# Aux_Power_Board_V1_1.net
KiCad netlist of a schematic drawn in EAGLE
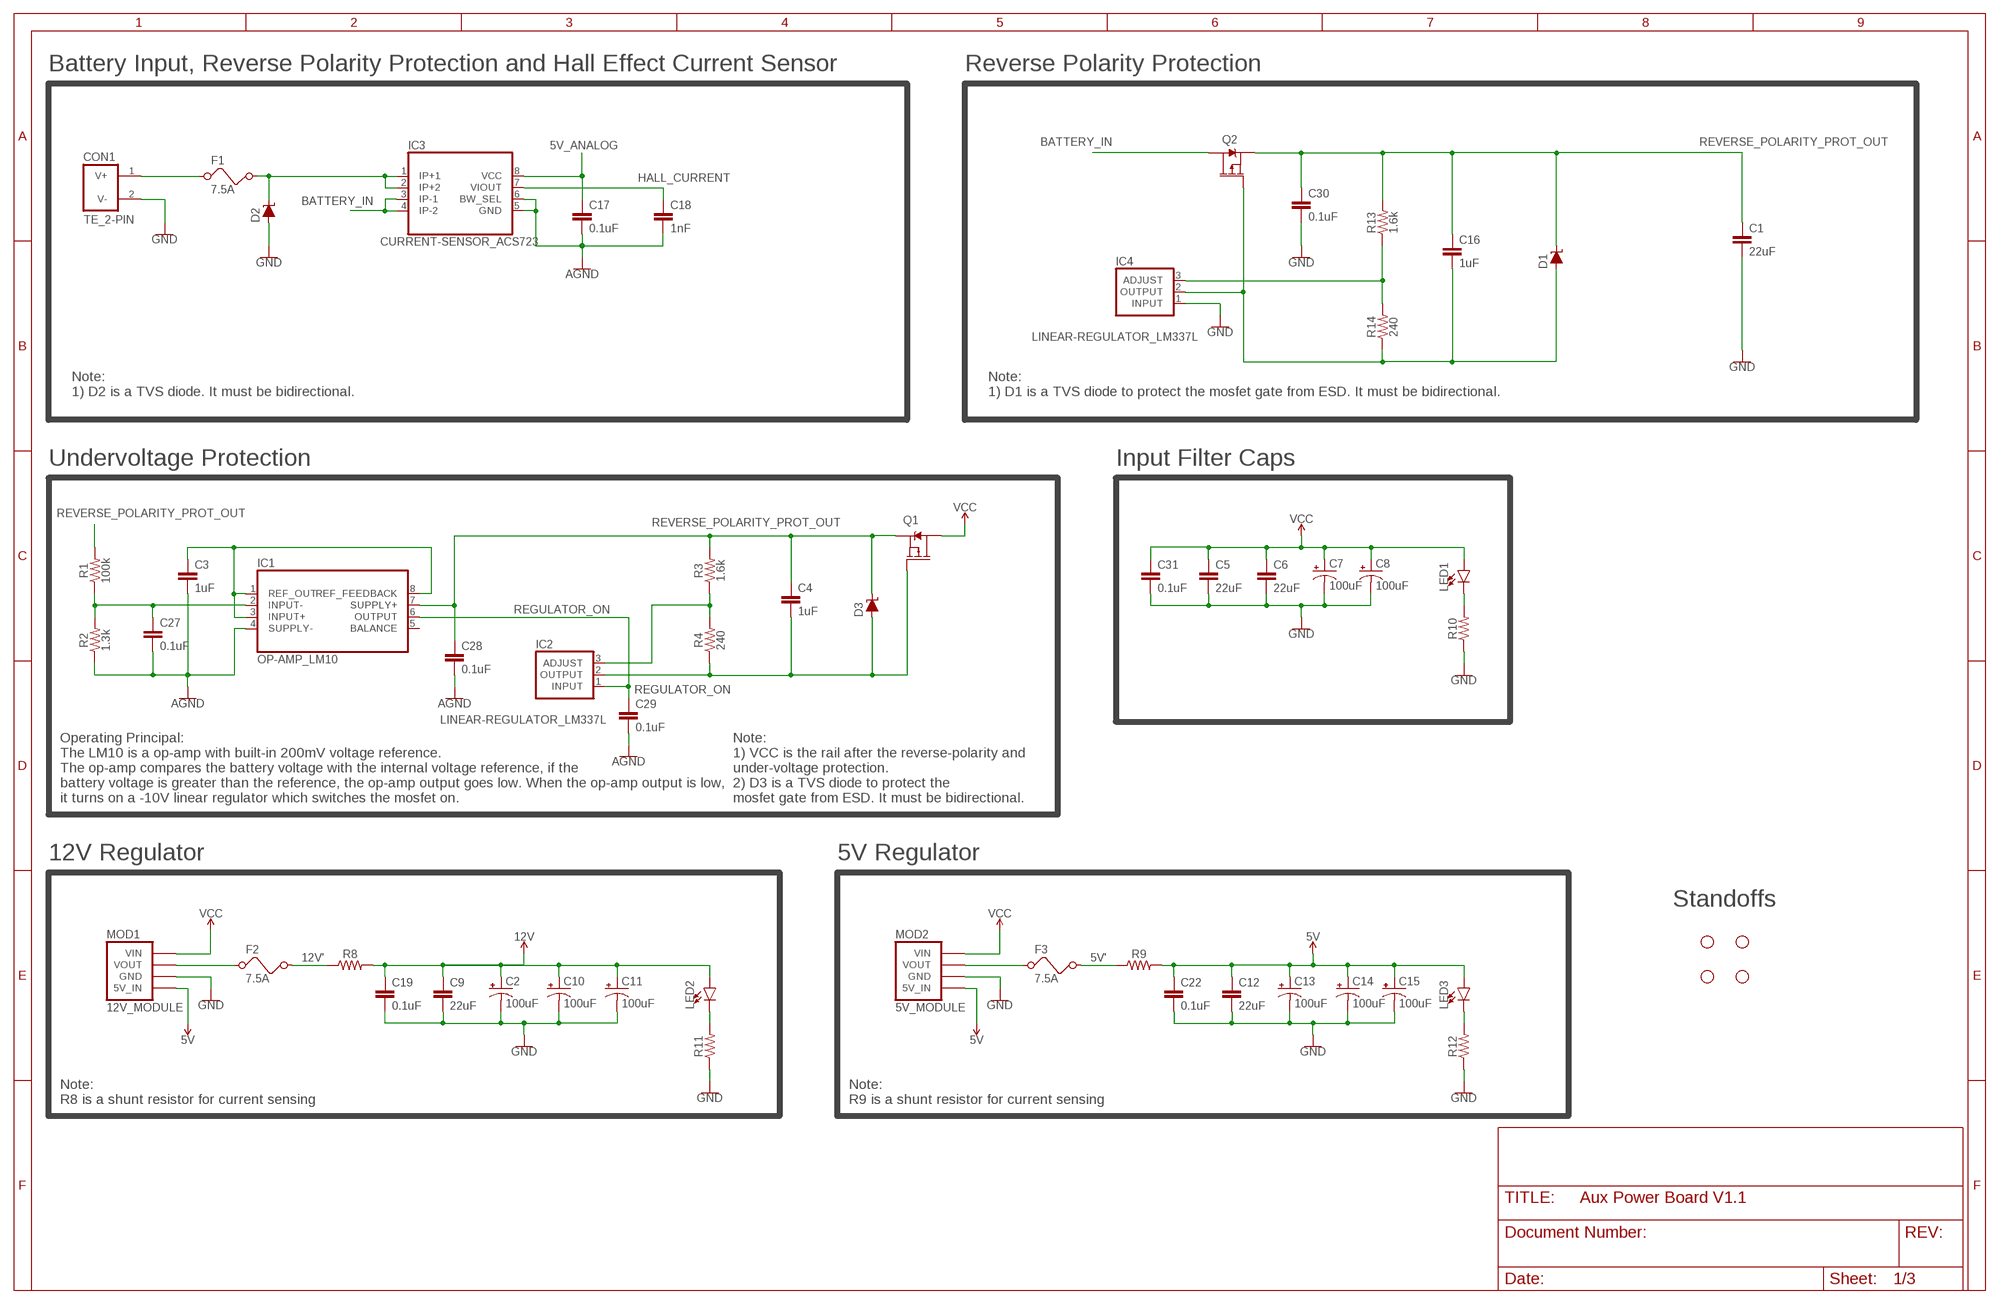
[diagram p0: schematic, sheet 1]
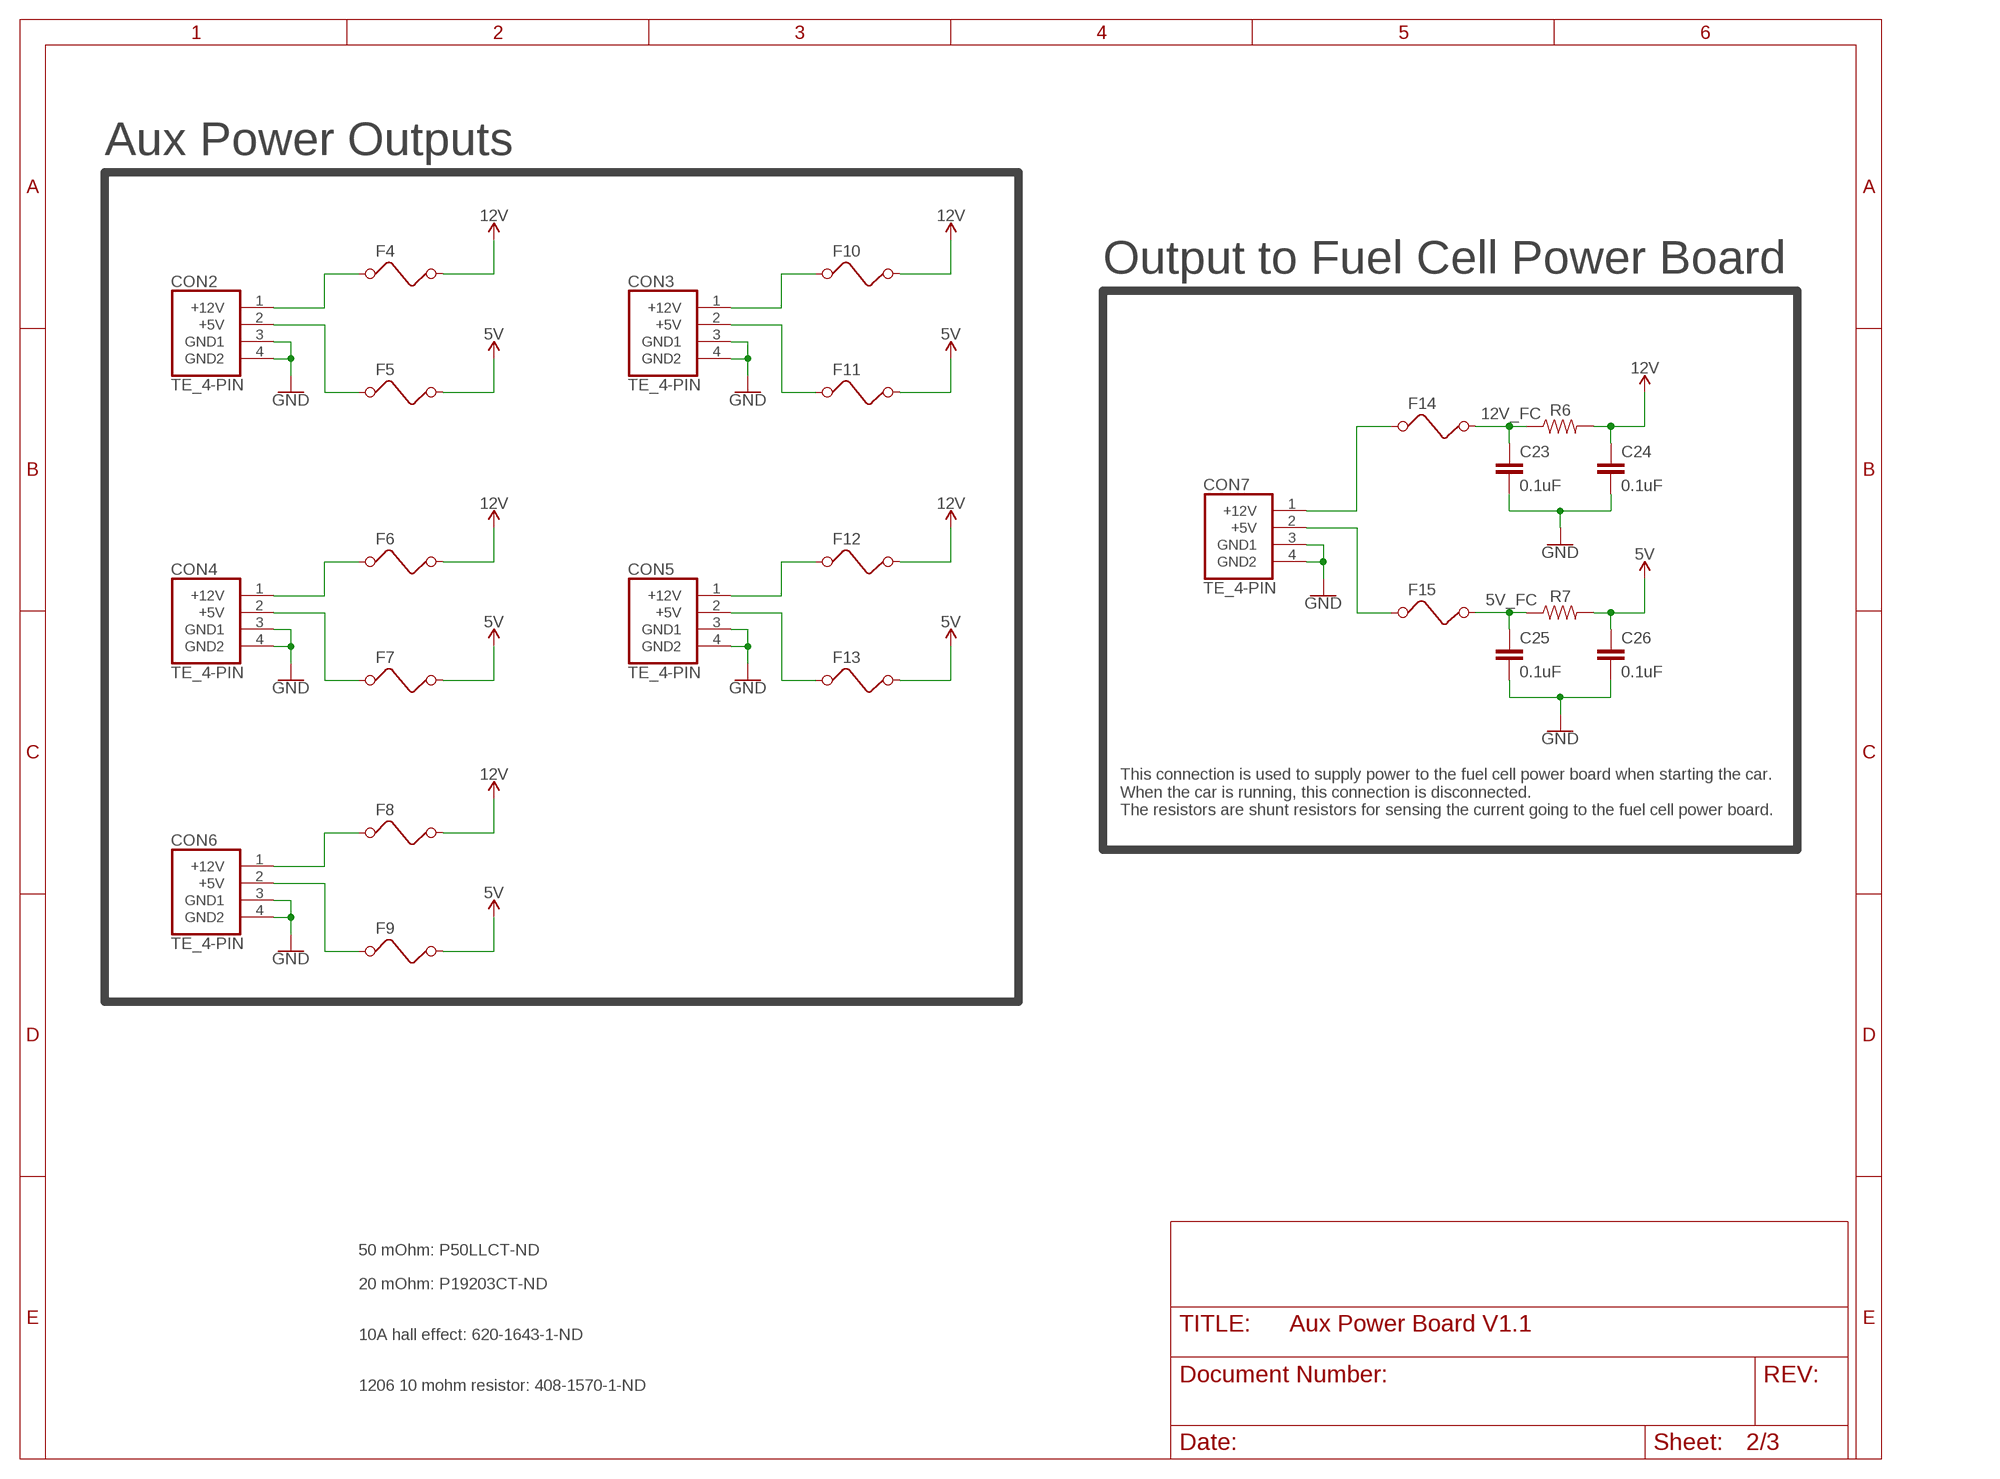
[diagram p1: schematic, sheet 2]
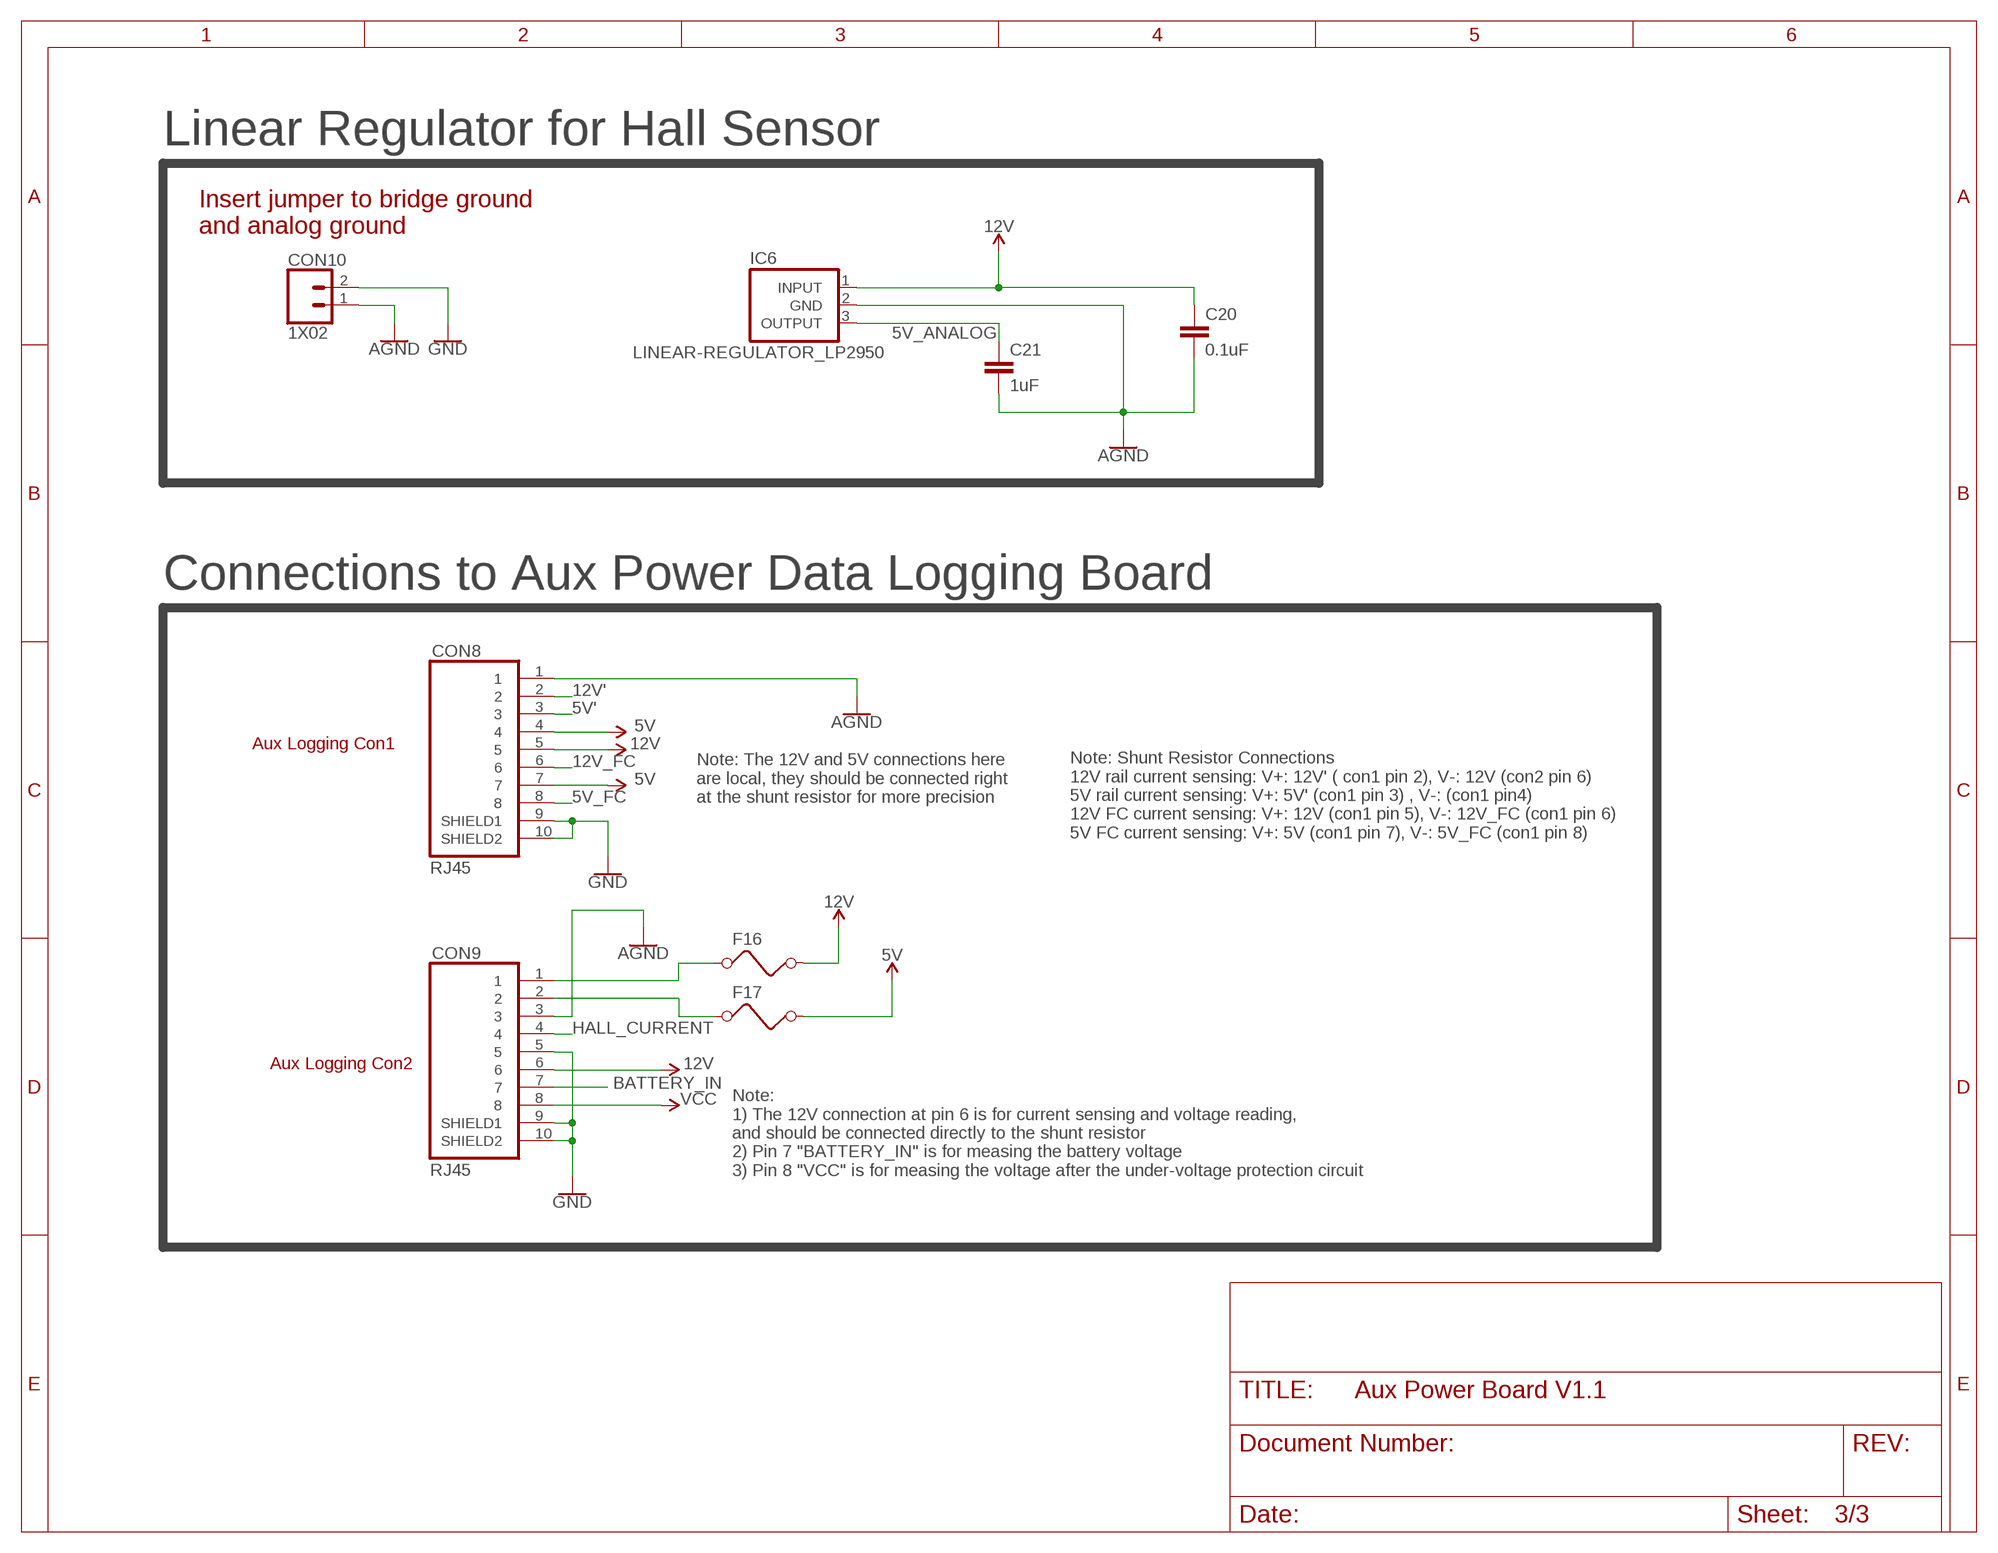
[diagram p2: schematic, sheet 3]

(export (version "E")
  (design (tool "Eeschema 10.0.6"))
  (components
    (comp (ref "C20")
      (value "0.1uF")
      (footprint "eagle-import:0805")
      (libsource (lib "eagle-import") (part "CAPACITOR_0805"))
    )
    (comp (ref "C21")
      (value "1uF")
      (footprint "eagle-import:0805")
      (libsource (lib "eagle-import") (part "CAPACITOR_0805"))
    )
    (comp (ref "CON8")
      (value "RJ45")
      (footprint "eagle-import:RJ45")
      (libsource (lib "eagle-import") (part "RJ45"))
    )
    (comp (ref "CON9")
      (value "RJ45")
      (footprint "eagle-import:RJ45")
      (libsource (lib "eagle-import") (part "RJ45"))
    )
    (comp (ref "CON10")
      (value "1X02")
      (footprint "eagle-import:1X02")
      (libsource (lib "eagle-import") (part "1X02"))
    )
    (comp (ref "F16")
      (value "FUSE_1210")
      (footprint "eagle-import:1210")
      (libsource (lib "eagle-import") (part "FUSE_1210"))
    )
    (comp (ref "F17")
      (value "FUSE_1210")
      (footprint "eagle-import:1210")
      (libsource (lib "eagle-import") (part "FUSE_1210"))
    )
    (comp (ref "IC6")
      (value "LINEAR-REGULATOR_LP2950")
      (footprint "eagle-import:TO92")
      (libsource (lib "eagle-import") (part "LINEAR-REGULATOR_LP2950"))
    )
    (comp (ref "C1")
      (value "22uF")
      (footprint "eagle-import:1210")
      (libsource (lib "eagle-import") (part "CAPACITOR_1210"))
    )
    (comp (ref "C2")
      (value "100uF")
      (footprint "eagle-import:CAPACITOR_100UF_50V")
      (libsource (lib "eagle-import") (part "CAPACITOR_ELECTROLYTIC_100UF"))
    )
    (comp (ref "C3")
      (value "1uF")
      (footprint "eagle-import:0805")
      (libsource (lib "eagle-import") (part "CAPACITOR_0805"))
    )
    (comp (ref "C4")
      (value "1uF")
      (footprint "eagle-import:0805")
      (libsource (lib "eagle-import") (part "CAPACITOR_0805"))
    )
    (comp (ref "C5")
      (value "22uF")
      (footprint "eagle-import:1210")
      (libsource (lib "eagle-import") (part "CAPACITOR_1210"))
    )
    (comp (ref "C6")
      (value "22uF")
      (footprint "eagle-import:1210")
      (libsource (lib "eagle-import") (part "CAPACITOR_1210"))
    )
    (comp (ref "C7")
      (value "100uF")
      (footprint "eagle-import:CAPACITOR_100UF_50V")
      (libsource (lib "eagle-import") (part "CAPACITOR_ELECTROLYTIC_100UF"))
    )
    (comp (ref "C8")
      (value "100uF")
      (footprint "eagle-import:CAPACITOR_100UF_50V")
      (libsource (lib "eagle-import") (part "CAPACITOR_ELECTROLYTIC_100UF"))
    )
    (comp (ref "C9")
      (value "22uF")
      (footprint "eagle-import:0805")
      (libsource (lib "eagle-import") (part "CAPACITOR_0805"))
    )
    (comp (ref "C10")
      (value "100uF")
      (footprint "eagle-import:CAPACITOR_100UF_50V")
      (libsource (lib "eagle-import") (part "CAPACITOR_ELECTROLYTIC_100UF"))
    )
    (comp (ref "C11")
      (value "100uF")
      (footprint "eagle-import:CAPACITOR_100UF_50V")
      (libsource (lib "eagle-import") (part "CAPACITOR_ELECTROLYTIC_100UF"))
    )
    (comp (ref "C12")
      (value "22uF")
      (footprint "eagle-import:0805")
      (libsource (lib "eagle-import") (part "CAPACITOR_0805"))
    )
    (comp (ref "C13")
      (value "100uF")
      (footprint "eagle-import:CAPACITOR_100UF_50V")
      (libsource (lib "eagle-import") (part "CAPACITOR_ELECTROLYTIC_100UF"))
    )
    (comp (ref "C14")
      (value "100uF")
      (footprint "eagle-import:CAPACITOR_100UF_50V")
      (libsource (lib "eagle-import") (part "CAPACITOR_ELECTROLYTIC_100UF"))
    )
    (comp (ref "C15")
      (value "100uF")
      (footprint "eagle-import:CAPACITOR_100UF_50V")
      (libsource (lib "eagle-import") (part "CAPACITOR_ELECTROLYTIC_100UF"))
    )
    (comp (ref "C16")
      (value "1uF")
      (footprint "eagle-import:0805")
      (libsource (lib "eagle-import") (part "CAPACITOR_0805"))
    )
    (comp (ref "C17")
      (value "0.1uF")
      (footprint "eagle-import:0805")
      (libsource (lib "eagle-import") (part "CAPACITOR_0805"))
    )
    (comp (ref "C18")
      (value "1nF")
      (footprint "eagle-import:0805")
      (libsource (lib "eagle-import") (part "CAPACITOR_0805"))
    )
    (comp (ref "C19")
      (value "0.1uF")
      (footprint "eagle-import:0805")
      (libsource (lib "eagle-import") (part "CAPACITOR_0805"))
    )
    (comp (ref "C22")
      (value "0.1uF")
      (footprint "eagle-import:0805")
      (libsource (lib "eagle-import") (part "CAPACITOR_0805"))
    )
    (comp (ref "C27")
      (value "0.1uF")
      (footprint "eagle-import:0805")
      (libsource (lib "eagle-import") (part "CAPACITOR_0805"))
    )
    (comp (ref "C28")
      (value "0.1uF")
      (footprint "eagle-import:0805")
      (libsource (lib "eagle-import") (part "CAPACITOR_0805"))
    )
    (comp (ref "C29")
      (value "0.1uF")
      (footprint "eagle-import:0805")
      (libsource (lib "eagle-import") (part "CAPACITOR_0805"))
    )
    (comp (ref "C30")
      (value "0.1uF")
      (footprint "eagle-import:0805")
      (libsource (lib "eagle-import") (part "CAPACITOR_0805"))
    )
    (comp (ref "C31")
      (value "0.1uF")
      (footprint "eagle-import:0805")
      (libsource (lib "eagle-import") (part "CAPACITOR_0805"))
    )
    (comp (ref "CON1")
      (value "TE_2-PIN")
      (footprint "eagle-import:TE_2-PIN")
      (libsource (lib "eagle-import") (part "TE_2-PIN"))
    )
    (comp (ref "D1")
      (value "DIODE_TVS_DO-214AA")
      (footprint "eagle-import:DO214AA")
      (libsource (lib "eagle-import") (part "DIODE_TVS_DO-214AA"))
    )
    (comp (ref "D2")
      (value "DIODE_TVS_DO-214AA")
      (footprint "eagle-import:DO214AA")
      (libsource (lib "eagle-import") (part "DIODE_TVS_DO-214AA"))
    )
    (comp (ref "D3")
      (value "DIODE_TVS_DO-214AA")
      (footprint "eagle-import:DO214AA")
      (libsource (lib "eagle-import") (part "DIODE_TVS_DO-214AA"))
    )
    (comp (ref "F1")
      (value "7.5A")
      (footprint "eagle-import:FUSEHOLDER_VERTICAL")
      (libsource (lib "eagle-import") (part "FUSEHOLDER_VERTICAL"))
    )
    (comp (ref "F2")
      (value "7.5A")
      (footprint "eagle-import:FUSEHOLDER_VERTICAL")
      (libsource (lib "eagle-import") (part "FUSEHOLDER_VERTICAL"))
    )
    (comp (ref "F3")
      (value "7.5A")
      (footprint "eagle-import:FUSEHOLDER_VERTICAL")
      (libsource (lib "eagle-import") (part "FUSEHOLDER_VERTICAL"))
    )
    (comp (ref "H1")
      (value "STAND-OFF")
      (footprint "eagle-import:STAND-OFF")
      (libsource (lib "eagle-import") (part "STAND-OFF"))
    )
    (comp (ref "H2")
      (value "STAND-OFF")
      (footprint "eagle-import:STAND-OFF")
      (libsource (lib "eagle-import") (part "STAND-OFF"))
    )
    (comp (ref "H3")
      (value "STAND-OFF")
      (footprint "eagle-import:STAND-OFF")
      (libsource (lib "eagle-import") (part "STAND-OFF"))
    )
    (comp (ref "H4")
      (value "STAND-OFF")
      (footprint "eagle-import:STAND-OFF")
      (libsource (lib "eagle-import") (part "STAND-OFF"))
    )
    (comp (ref "IC1")
      (value "OP-AMP_LM10")
      (footprint "eagle-import:DIP08")
      (libsource (lib "eagle-import") (part "OP-AMP_LM10"))
    )
    (comp (ref "IC2")
      (value "LINEAR-REGULATOR_LM337L")
      (footprint "eagle-import:TO92")
      (libsource (lib "eagle-import") (part "LINEAR-REGULATOR_LM337L"))
    )
    (comp (ref "IC3")
      (value "CURRENT-SENSOR_ACS723")
      (footprint "eagle-import:SOIC8")
      (libsource (lib "eagle-import") (part "CURRENT-SENSOR_ACS723"))
    )
    (comp (ref "IC4")
      (value "LINEAR-REGULATOR_LM337L")
      (footprint "eagle-import:TO92")
      (libsource (lib "eagle-import") (part "LINEAR-REGULATOR_LM337L"))
    )
    (comp (ref "LED1")
      (value "LED_0805")
      (footprint "eagle-import:0805_LED")
      (libsource (lib "eagle-import") (part "LED_0805"))
    )
    (comp (ref "LED2")
      (value "LED_0805")
      (footprint "eagle-import:0805_LED")
      (libsource (lib "eagle-import") (part "LED_0805"))
    )
    (comp (ref "LED3")
      (value "LED_0805")
      (footprint "eagle-import:0805_LED")
      (libsource (lib "eagle-import") (part "LED_0805"))
    )
    (comp (ref "MOD1")
      (value "12V_MODULE")
      (footprint "eagle-import:5_12V_MODULE")
      (libsource (lib "eagle-import") (part "12V_MODULE"))
    )
    (comp (ref "MOD2")
      (value "5V_MODULE")
      (footprint "eagle-import:5_12V_MODULE")
      (libsource (lib "eagle-import") (part "5V_MODULE"))
    )
    (comp (ref "Q1")
      (value "MOSFET_PMOS_TO-263")
      (footprint "eagle-import:TO-263_D2PAK")
      (libsource (lib "eagle-import") (part "MOSFET_PMOS_TO-263"))
    )
    (comp (ref "Q2")
      (value "MOSFET_PMOS_TO-263")
      (footprint "eagle-import:TO-263_D2PAK")
      (libsource (lib "eagle-import") (part "MOSFET_PMOS_TO-263"))
    )
    (comp (ref "R1")
      (value "100k")
      (footprint "eagle-import:0805")
      (libsource (lib "eagle-import") (part "RESISTOR_0805"))
    )
    (comp (ref "R2")
      (value "1.3k")
      (footprint "eagle-import:0805")
      (libsource (lib "eagle-import") (part "RESISTOR_0805"))
    )
    (comp (ref "R3")
      (value "1.6k")
      (footprint "eagle-import:0805")
      (libsource (lib "eagle-import") (part "RESISTOR_0805"))
    )
    (comp (ref "R4")
      (value "240")
      (footprint "eagle-import:0805")
      (libsource (lib "eagle-import") (part "RESISTOR_0805"))
    )
    (comp (ref "R8")
      (value "RESISTOR_1210")
      (footprint "eagle-import:1210")
      (libsource (lib "eagle-import") (part "RESISTOR_1210"))
    )
    (comp (ref "R9")
      (value "RESISTOR_1210")
      (footprint "eagle-import:1210")
      (libsource (lib "eagle-import") (part "RESISTOR_1210"))
    )
    (comp (ref "R10")
      (value "RESISTOR_0805")
      (footprint "eagle-import:0805")
      (libsource (lib "eagle-import") (part "RESISTOR_0805"))
    )
    (comp (ref "R11")
      (value "RESISTOR_0805")
      (footprint "eagle-import:0805")
      (libsource (lib "eagle-import") (part "RESISTOR_0805"))
    )
    (comp (ref "R12")
      (value "RESISTOR_0805")
      (footprint "eagle-import:0805")
      (libsource (lib "eagle-import") (part "RESISTOR_0805"))
    )
    (comp (ref "R13")
      (value "1.6k")
      (footprint "eagle-import:0805")
      (libsource (lib "eagle-import") (part "RESISTOR_0805"))
    )
    (comp (ref "R14")
      (value "240")
      (footprint "eagle-import:0805")
      (libsource (lib "eagle-import") (part "RESISTOR_0805"))
    )
    (comp (ref "C23")
      (value "0.1uF")
      (footprint "eagle-import:0805")
      (libsource (lib "eagle-import") (part "CAPACITOR_0805"))
    )
    (comp (ref "C24")
      (value "0.1uF")
      (footprint "eagle-import:0805")
      (libsource (lib "eagle-import") (part "CAPACITOR_0805"))
    )
    (comp (ref "C25")
      (value "0.1uF")
      (footprint "eagle-import:0805")
      (libsource (lib "eagle-import") (part "CAPACITOR_0805"))
    )
    (comp (ref "C26")
      (value "0.1uF")
      (footprint "eagle-import:0805")
      (libsource (lib "eagle-import") (part "CAPACITOR_0805"))
    )
    (comp (ref "CON2")
      (value "TE_4-PIN")
      (footprint "eagle-import:TE_4-PIN")
      (libsource (lib "eagle-import") (part "TE_4-PIN"))
    )
    (comp (ref "CON3")
      (value "TE_4-PIN")
      (footprint "eagle-import:TE_4-PIN")
      (libsource (lib "eagle-import") (part "TE_4-PIN"))
    )
    (comp (ref "CON4")
      (value "TE_4-PIN")
      (footprint "eagle-import:TE_4-PIN")
      (libsource (lib "eagle-import") (part "TE_4-PIN"))
    )
    (comp (ref "CON5")
      (value "TE_4-PIN")
      (footprint "eagle-import:TE_4-PIN")
      (libsource (lib "eagle-import") (part "TE_4-PIN"))
    )
    (comp (ref "CON6")
      (value "TE_4-PIN")
      (footprint "eagle-import:TE_4-PIN")
      (libsource (lib "eagle-import") (part "TE_4-PIN"))
    )
    (comp (ref "CON7")
      (value "TE_4-PIN")
      (footprint "eagle-import:TE_4-PIN")
      (libsource (lib "eagle-import") (part "TE_4-PIN"))
    )
    (comp (ref "F4")
      (value "FUSE_1210")
      (footprint "eagle-import:1210")
      (libsource (lib "eagle-import") (part "FUSE_1210"))
    )
    (comp (ref "F5")
      (value "FUSE_1210")
      (footprint "eagle-import:1210")
      (libsource (lib "eagle-import") (part "FUSE_1210"))
    )
    (comp (ref "F6")
      (value "FUSE_1210")
      (footprint "eagle-import:1210")
      (libsource (lib "eagle-import") (part "FUSE_1210"))
    )
    (comp (ref "F7")
      (value "FUSE_1210")
      (footprint "eagle-import:1210")
      (libsource (lib "eagle-import") (part "FUSE_1210"))
    )
    (comp (ref "F8")
      (value "FUSE_1210")
      (footprint "eagle-import:1210")
      (libsource (lib "eagle-import") (part "FUSE_1210"))
    )
    (comp (ref "F9")
      (value "FUSE_1210")
      (footprint "eagle-import:1210")
      (libsource (lib "eagle-import") (part "FUSE_1210"))
    )
    (comp (ref "F10")
      (value "FUSE_1210")
      (footprint "eagle-import:1210")
      (libsource (lib "eagle-import") (part "FUSE_1210"))
    )
    (comp (ref "F11")
      (value "FUSE_1210")
      (footprint "eagle-import:1210")
      (libsource (lib "eagle-import") (part "FUSE_1210"))
    )
    (comp (ref "F12")
      (value "FUSE_1210")
      (footprint "eagle-import:1210")
      (libsource (lib "eagle-import") (part "FUSE_1210"))
    )
    (comp (ref "F13")
      (value "FUSE_1210")
      (footprint "eagle-import:1210")
      (libsource (lib "eagle-import") (part "FUSE_1210"))
    )
    (comp (ref "F14")
      (value "FUSE_1210")
      (footprint "eagle-import:1210")
      (libsource (lib "eagle-import") (part "FUSE_1210"))
    )
    (comp (ref "F15")
      (value "FUSE_1210")
      (footprint "eagle-import:1210")
      (libsource (lib "eagle-import") (part "FUSE_1210"))
    )
    (comp (ref "R6")
      (value "RESISTOR_1210")
      (footprint "eagle-import:1210")
      (libsource (lib "eagle-import") (part "RESISTOR_1210"))
    )
    (comp (ref "R7")
      (value "RESISTOR_1210")
      (footprint "eagle-import:1210")
      (libsource (lib "eagle-import") (part "RESISTOR_1210"))
    )
  )
  (nets
    (net (code "1") (name "5V") (class "Default")
      (node (ref "C12") (pin "1") (pinfunction "1_1") (pintype "passive"))
      (node (ref "C13") (pin "+") (pinfunction "+_+") (pintype "passive"))
      (node (ref "C14") (pin "+") (pinfunction "+_+") (pintype "passive"))
      (node (ref "C15") (pin "+") (pinfunction "+_+") (pintype "passive"))
      (node (ref "C22") (pin "1") (pinfunction "1_1") (pintype "passive"))
      (node (ref "C26") (pin "1") (pinfunction "1_1") (pintype "passive"))
      (node (ref "CON8") (pin "4") (pinfunction "4_4") (pintype "passive"))
      (node (ref "CON8") (pin "7") (pinfunction "7_7") (pintype "passive"))
      (node (ref "F11") (pin "2") (pinfunction "2_2") (pintype "passive"))
      (node (ref "F13") (pin "2") (pinfunction "2_2") (pintype "passive"))
      (node (ref "F17") (pin "2") (pinfunction "2_2") (pintype "passive"))
      (node (ref "F5") (pin "2") (pinfunction "2_2") (pintype "passive"))
      (node (ref "F7") (pin "2") (pinfunction "2_2") (pintype "passive"))
      (node (ref "F9") (pin "2") (pinfunction "2_2") (pintype "passive"))
      (node (ref "LED3") (pin "1") (pinfunction "A_1") (pintype "passive"))
      (node (ref "MOD1") (pin "P$32") (pinfunction "5V_IN_P$32") (pintype "bidirectional"))
      (node (ref "MOD2") (pin "P$32") (pinfunction "5V_IN_P$32") (pintype "bidirectional"))
      (node (ref "R7") (pin "2") (pinfunction "2_2") (pintype "passive"))
      (node (ref "R9") (pin "2") (pinfunction "2_2") (pintype "passive"))
    )
    (net (code "2") (name "5V'") (class "Default")
      (node (ref "CON8") (pin "3") (pinfunction "3_3") (pintype "passive"))
      (node (ref "F3") (pin "3") (pinfunction "2_3") (pintype "passive"))
      (node (ref "F3") (pin "4") (pinfunction "2_4") (pintype "passive"))
      (node (ref "R9") (pin "1") (pinfunction "1_1") (pintype "passive"))
    )
    (net (code "3") (name "5V_ANALOG") (class "Default")
      (node (ref "C17") (pin "1") (pinfunction "1_1") (pintype "passive"))
      (node (ref "C21") (pin "1") (pinfunction "1_1") (pintype "passive"))
      (node (ref "IC3") (pin "8") (pinfunction "VCC_8") (pintype "bidirectional"))
      (node (ref "IC6") (pin "3") (pinfunction "OUTPUT_3") (pintype "bidirectional"))
    )
    (net (code "4") (name "5V_FC") (class "Default")
      (node (ref "C25") (pin "1") (pinfunction "1_1") (pintype "passive"))
      (node (ref "CON8") (pin "8") (pinfunction "8_8") (pintype "passive"))
      (node (ref "F15") (pin "2") (pinfunction "2_2") (pintype "passive"))
      (node (ref "R7") (pin "1") (pinfunction "1_1") (pintype "passive"))
    )
    (net (code "5") (name "12V") (class "Default")
      (node (ref "C10") (pin "+") (pinfunction "+_+") (pintype "passive"))
      (node (ref "C11") (pin "+") (pinfunction "+_+") (pintype "passive"))
      (node (ref "C19") (pin "1") (pinfunction "1_1") (pintype "passive"))
      (node (ref "C2") (pin "+") (pinfunction "+_+") (pintype "passive"))
      (node (ref "C20") (pin "1") (pinfunction "1_1") (pintype "passive"))
      (node (ref "C24") (pin "1") (pinfunction "1_1") (pintype "passive"))
      (node (ref "C9") (pin "1") (pinfunction "1_1") (pintype "passive"))
      (node (ref "CON8") (pin "5") (pinfunction "5_5") (pintype "passive"))
      (node (ref "CON9") (pin "6") (pinfunction "6_6") (pintype "passive"))
      (node (ref "F10") (pin "2") (pinfunction "2_2") (pintype "passive"))
      (node (ref "F12") (pin "2") (pinfunction "2_2") (pintype "passive"))
      (node (ref "F16") (pin "2") (pinfunction "2_2") (pintype "passive"))
      (node (ref "F4") (pin "2") (pinfunction "2_2") (pintype "passive"))
      (node (ref "F6") (pin "2") (pinfunction "2_2") (pintype "passive"))
      (node (ref "F8") (pin "2") (pinfunction "2_2") (pintype "passive"))
      (node (ref "IC6") (pin "1") (pinfunction "INPUT_1") (pintype "bidirectional"))
      (node (ref "LED2") (pin "1") (pinfunction "A_1") (pintype "passive"))
      (node (ref "R6") (pin "2") (pinfunction "2_2") (pintype "passive"))
      (node (ref "R8") (pin "2") (pinfunction "2_2") (pintype "passive"))
    )
    (net (code "6") (name "12V'") (class "Default")
      (node (ref "CON8") (pin "2") (pinfunction "2_2") (pintype "passive"))
      (node (ref "F2") (pin "3") (pinfunction "2_3") (pintype "passive"))
      (node (ref "F2") (pin "4") (pinfunction "2_4") (pintype "passive"))
      (node (ref "R8") (pin "1") (pinfunction "1_1") (pintype "passive"))
    )
    (net (code "7") (name "12V_FC") (class "Default")
      (node (ref "C23") (pin "1") (pinfunction "1_1") (pintype "passive"))
      (node (ref "CON8") (pin "6") (pinfunction "6_6") (pintype "passive"))
      (node (ref "F14") (pin "2") (pinfunction "2_2") (pintype "passive"))
      (node (ref "R6") (pin "1") (pinfunction "1_1") (pintype "passive"))
    )
    (net (code "8") (name "AGND") (class "Default")
      (node (ref "C17") (pin "2") (pinfunction "2_2") (pintype "passive"))
      (node (ref "C18") (pin "2") (pinfunction "2_2") (pintype "passive"))
      (node (ref "C20") (pin "2") (pinfunction "2_2") (pintype "passive"))
      (node (ref "C21") (pin "2") (pinfunction "2_2") (pintype "passive"))
      (node (ref "C27") (pin "2") (pinfunction "2_2") (pintype "passive"))
      (node (ref "C28") (pin "2") (pinfunction "2_2") (pintype "passive"))
      (node (ref "C29") (pin "2") (pinfunction "2_2") (pintype "passive"))
      (node (ref "C3") (pin "2") (pinfunction "2_2") (pintype "passive"))
      (node (ref "CON10") (pin "1") (pinfunction "1_1") (pintype "passive"))
      (node (ref "CON8") (pin "1") (pinfunction "1_1") (pintype "passive"))
      (node (ref "CON9") (pin "3") (pinfunction "3_3") (pintype "passive"))
      (node (ref "IC1") (pin "4") (pinfunction "SUPPLY-_4") (pintype "bidirectional"))
      (node (ref "IC3") (pin "5") (pinfunction "GND_5") (pintype "bidirectional"))
      (node (ref "IC3") (pin "6") (pinfunction "BW_SEL_6") (pintype "bidirectional"))
      (node (ref "IC6") (pin "2") (pinfunction "GND_2") (pintype "bidirectional"))
      (node (ref "R2") (pin "1") (pinfunction "1_1") (pintype "passive"))
    )
    (net (code "9") (name "BATTERY_IN") (class "Default")
      (node (ref "CON9") (pin "7") (pinfunction "7_7") (pintype "passive"))
      (node (ref "IC3") (pin "3") (pinfunction "IP-1_3") (pintype "bidirectional"))
      (node (ref "IC3") (pin "4") (pinfunction "IP-2_4") (pintype "bidirectional"))
      (node (ref "Q2") (pin "2") (pinfunction "D_2") (pintype "bidirectional"))
    )
    (net (code "10") (name "GND") (class "Default")
      (node (ref "C1") (pin "2") (pinfunction "2_2") (pintype "passive"))
      (node (ref "C10") (pin "-") (pinfunction "-_-") (pintype "passive"))
      (node (ref "C11") (pin "-") (pinfunction "-_-") (pintype "passive"))
      (node (ref "C12") (pin "2") (pinfunction "2_2") (pintype "passive"))
      (node (ref "C13") (pin "-") (pinfunction "-_-") (pintype "passive"))
      (node (ref "C14") (pin "-") (pinfunction "-_-") (pintype "passive"))
      (node (ref "C15") (pin "-") (pinfunction "-_-") (pintype "passive"))
      (node (ref "C19") (pin "2") (pinfunction "2_2") (pintype "passive"))
      (node (ref "C2") (pin "-") (pinfunction "-_-") (pintype "passive"))
      (node (ref "C22") (pin "2") (pinfunction "2_2") (pintype "passive"))
      (node (ref "C23") (pin "2") (pinfunction "2_2") (pintype "passive"))
      (node (ref "C24") (pin "2") (pinfunction "2_2") (pintype "passive"))
      (node (ref "C25") (pin "2") (pinfunction "2_2") (pintype "passive"))
      (node (ref "C26") (pin "2") (pinfunction "2_2") (pintype "passive"))
      (node (ref "C30") (pin "2") (pinfunction "2_2") (pintype "passive"))
      (node (ref "C31") (pin "2") (pinfunction "2_2") (pintype "passive"))
      (node (ref "C5") (pin "2") (pinfunction "2_2") (pintype "passive"))
      (node (ref "C6") (pin "2") (pinfunction "2_2") (pintype "passive"))
      (node (ref "C7") (pin "-") (pinfunction "-_-") (pintype "passive"))
      (node (ref "C8") (pin "-") (pinfunction "-_-") (pintype "passive"))
      (node (ref "C9") (pin "2") (pinfunction "2_2") (pintype "passive"))
      (node (ref "CON1") (pin "2") (pinfunction "V-_2") (pintype "passive"))
      (node (ref "CON10") (pin "2") (pinfunction "2_2") (pintype "passive"))
      (node (ref "CON2") (pin "3") (pinfunction "GND1_3") (pintype "passive"))
      (node (ref "CON2") (pin "4") (pinfunction "GND2_4") (pintype "passive"))
      (node (ref "CON3") (pin "3") (pinfunction "GND1_3") (pintype "passive"))
      (node (ref "CON3") (pin "4") (pinfunction "GND2_4") (pintype "passive"))
      (node (ref "CON4") (pin "3") (pinfunction "GND1_3") (pintype "passive"))
      (node (ref "CON4") (pin "4") (pinfunction "GND2_4") (pintype "passive"))
      (node (ref "CON5") (pin "3") (pinfunction "GND1_3") (pintype "passive"))
      (node (ref "CON5") (pin "4") (pinfunction "GND2_4") (pintype "passive"))
      (node (ref "CON6") (pin "3") (pinfunction "GND1_3") (pintype "passive"))
      (node (ref "CON6") (pin "4") (pinfunction "GND2_4") (pintype "passive"))
      (node (ref "CON7") (pin "3") (pinfunction "GND1_3") (pintype "passive"))
      (node (ref "CON7") (pin "4") (pinfunction "GND2_4") (pintype "passive"))
      (node (ref "CON8") (pin "10") (pinfunction "SHIELD2_10") (pintype "passive"))
      (node (ref "CON8") (pin "9") (pinfunction "SHIELD1_9") (pintype "passive"))
      (node (ref "CON9") (pin "10") (pinfunction "SHIELD2_10") (pintype "passive"))
      (node (ref "CON9") (pin "5") (pinfunction "5_5") (pintype "passive"))
      (node (ref "CON9") (pin "9") (pinfunction "SHIELD1_9") (pintype "passive"))
      (node (ref "D2") (pin "A") (pinfunction "A_A") (pintype "passive"))
      (node (ref "IC4") (pin "1") (pinfunction "INPUT_1") (pintype "bidirectional"))
      (node (ref "MOD1") (pin "P$25") (pinfunction "GND_P$25") (pintype "passive"))
      (node (ref "MOD1") (pin "P$26") (pinfunction "GND_P$26") (pintype "passive"))
      (node (ref "MOD1") (pin "P$27") (pinfunction "GND_P$27") (pintype "passive"))
      (node (ref "MOD1") (pin "P$28") (pinfunction "GND_P$28") (pintype "passive"))
      (node (ref "MOD1") (pin "P$29") (pinfunction "GND_P$29") (pintype "passive"))
      (node (ref "MOD1") (pin "P$30") (pinfunction "GND_P$30") (pintype "passive"))
      (node (ref "MOD1") (pin "P$31") (pinfunction "GND_P$31") (pintype "passive"))
      (node (ref "MOD2") (pin "P$25") (pinfunction "GND_P$25") (pintype "passive"))
      (node (ref "MOD2") (pin "P$26") (pinfunction "GND_P$26") (pintype "passive"))
      (node (ref "MOD2") (pin "P$27") (pinfunction "GND_P$27") (pintype "passive"))
      (node (ref "MOD2") (pin "P$28") (pinfunction "GND_P$28") (pintype "passive"))
      (node (ref "MOD2") (pin "P$29") (pinfunction "GND_P$29") (pintype "passive"))
      (node (ref "MOD2") (pin "P$30") (pinfunction "GND_P$30") (pintype "passive"))
      (node (ref "MOD2") (pin "P$31") (pinfunction "GND_P$31") (pintype "passive"))
      (node (ref "R10") (pin "1") (pinfunction "1_1") (pintype "passive"))
      (node (ref "R11") (pin "1") (pinfunction "1_1") (pintype "passive"))
      (node (ref "R12") (pin "1") (pinfunction "1_1") (pintype "passive"))
    )
    (net (code "11") (name "HALL_CURRENT") (class "Default")
      (node (ref "C18") (pin "1") (pinfunction "1_1") (pintype "passive"))
      (node (ref "CON9") (pin "4") (pinfunction "4_4") (pintype "passive"))
      (node (ref "IC3") (pin "7") (pinfunction "VIOUT_7") (pintype "bidirectional"))
    )
    (net (code "12") (name "Net-(CON1-V+)") (class "Default")
      (node (ref "CON1") (pin "1") (pinfunction "V+_1") (pintype "passive"))
      (node (ref "F1") (pin "1") (pinfunction "1_1") (pintype "passive"))
      (node (ref "F1") (pin "2") (pinfunction "1_2") (pintype "passive"))
    )
    (net (code "13") (name "Net-(CON2-+5V)") (class "Default")
      (node (ref "CON2") (pin "2") (pinfunction "+5V_2") (pintype "passive"))
      (node (ref "F5") (pin "1") (pinfunction "1_1") (pintype "passive"))
    )
    (net (code "14") (name "Net-(CON2-+12V)") (class "Default")
      (node (ref "CON2") (pin "1") (pinfunction "+12V_1") (pintype "passive"))
      (node (ref "F4") (pin "1") (pinfunction "1_1") (pintype "passive"))
    )
    (net (code "15") (name "Net-(CON3-+5V)") (class "Default")
      (node (ref "CON3") (pin "2") (pinfunction "+5V_2") (pintype "passive"))
      (node (ref "F11") (pin "1") (pinfunction "1_1") (pintype "passive"))
    )
    (net (code "16") (name "Net-(CON3-+12V)") (class "Default")
      (node (ref "CON3") (pin "1") (pinfunction "+12V_1") (pintype "passive"))
      (node (ref "F10") (pin "1") (pinfunction "1_1") (pintype "passive"))
    )
    (net (code "17") (name "Net-(CON4-+5V)") (class "Default")
      (node (ref "CON4") (pin "2") (pinfunction "+5V_2") (pintype "passive"))
      (node (ref "F7") (pin "1") (pinfunction "1_1") (pintype "passive"))
    )
    (net (code "18") (name "Net-(CON4-+12V)") (class "Default")
      (node (ref "CON4") (pin "1") (pinfunction "+12V_1") (pintype "passive"))
      (node (ref "F6") (pin "1") (pinfunction "1_1") (pintype "passive"))
    )
    (net (code "19") (name "Net-(CON5-+5V)") (class "Default")
      (node (ref "CON5") (pin "2") (pinfunction "+5V_2") (pintype "passive"))
      (node (ref "F13") (pin "1") (pinfunction "1_1") (pintype "passive"))
    )
    (net (code "20") (name "Net-(CON5-+12V)") (class "Default")
      (node (ref "CON5") (pin "1") (pinfunction "+12V_1") (pintype "passive"))
      (node (ref "F12") (pin "1") (pinfunction "1_1") (pintype "passive"))
    )
    (net (code "21") (name "Net-(CON6-+5V)") (class "Default")
      (node (ref "CON6") (pin "2") (pinfunction "+5V_2") (pintype "passive"))
      (node (ref "F9") (pin "1") (pinfunction "1_1") (pintype "passive"))
    )
    (net (code "22") (name "Net-(CON6-+12V)") (class "Default")
      (node (ref "CON6") (pin "1") (pinfunction "+12V_1") (pintype "passive"))
      (node (ref "F8") (pin "1") (pinfunction "1_1") (pintype "passive"))
    )
    (net (code "23") (name "Net-(CON7-+5V)") (class "Default")
      (node (ref "CON7") (pin "2") (pinfunction "+5V_2") (pintype "passive"))
      (node (ref "F15") (pin "1") (pinfunction "1_1") (pintype "passive"))
    )
    (net (code "24") (name "Net-(CON7-+12V)") (class "Default")
      (node (ref "CON7") (pin "1") (pinfunction "+12V_1") (pintype "passive"))
      (node (ref "F14") (pin "1") (pinfunction "1_1") (pintype "passive"))
    )
    (net (code "25") (name "Net-(CON9-Pad1)") (class "Default")
      (node (ref "CON9") (pin "1") (pinfunction "1_1") (pintype "passive"))
      (node (ref "F16") (pin "1") (pinfunction "1_1") (pintype "passive"))
    )
    (net (code "26") (name "Net-(CON9-Pad2)") (class "Default")
      (node (ref "CON9") (pin "2") (pinfunction "2_2") (pintype "passive"))
      (node (ref "F17") (pin "1") (pinfunction "1_1") (pintype "passive"))
    )
    (net (code "27") (name "Net-(F2-1-Pad2)") (class "Default")
      (node (ref "F2") (pin "1") (pinfunction "1_1") (pintype "passive"))
      (node (ref "F2") (pin "2") (pinfunction "1_2") (pintype "passive"))
      (node (ref "MOD1") (pin "P$10") (pinfunction "VOUT_P$10") (pintype "passive"))
      (node (ref "MOD1") (pin "P$11") (pinfunction "VOUT_P$11") (pintype "passive"))
      (node (ref "MOD1") (pin "P$12") (pinfunction "VOUT_P$12") (pintype "passive"))
      (node (ref "MOD1") (pin "P$13") (pinfunction "VOUT_P$13") (pintype "passive"))
      (node (ref "MOD1") (pin "P$14") (pinfunction "VOUT_P$14") (pintype "passive"))
      (node (ref "MOD1") (pin "P$15") (pinfunction "VOUT_P$15") (pintype "passive"))
      (node (ref "MOD1") (pin "P$16") (pinfunction "VOUT_P$16") (pintype "passive"))
      (node (ref "MOD1") (pin "P$17") (pinfunction "VOUT_P$17") (pintype "passive"))
      (node (ref "MOD1") (pin "P$18") (pinfunction "VOUT_P$18") (pintype "passive"))
      (node (ref "MOD1") (pin "P$19") (pinfunction "VOUT_P$19") (pintype "passive"))
      (node (ref "MOD1") (pin "P$20") (pinfunction "VOUT_P$20") (pintype "passive"))
      (node (ref "MOD1") (pin "P$21") (pinfunction "VOUT_P$21") (pintype "passive"))
      (node (ref "MOD1") (pin "P$22") (pinfunction "VOUT_P$22") (pintype "passive"))
      (node (ref "MOD1") (pin "P$23") (pinfunction "VOUT_P$23") (pintype "passive"))
      (node (ref "MOD1") (pin "P$24") (pinfunction "VOUT_P$24") (pintype "passive"))
      (node (ref "MOD1") (pin "P$9") (pinfunction "VOUT_P$9") (pintype "passive"))
    )
    (net (code "28") (name "Net-(F3-1-Pad2)") (class "Default")
      (node (ref "F3") (pin "1") (pinfunction "1_1") (pintype "passive"))
      (node (ref "F3") (pin "2") (pinfunction "1_2") (pintype "passive"))
      (node (ref "MOD2") (pin "P$10") (pinfunction "VOUT_P$10") (pintype "passive"))
      (node (ref "MOD2") (pin "P$11") (pinfunction "VOUT_P$11") (pintype "passive"))
      (node (ref "MOD2") (pin "P$12") (pinfunction "VOUT_P$12") (pintype "passive"))
      (node (ref "MOD2") (pin "P$13") (pinfunction "VOUT_P$13") (pintype "passive"))
      (node (ref "MOD2") (pin "P$14") (pinfunction "VOUT_P$14") (pintype "passive"))
      (node (ref "MOD2") (pin "P$15") (pinfunction "VOUT_P$15") (pintype "passive"))
      (node (ref "MOD2") (pin "P$16") (pinfunction "VOUT_P$16") (pintype "passive"))
      (node (ref "MOD2") (pin "P$17") (pinfunction "VOUT_P$17") (pintype "passive"))
      (node (ref "MOD2") (pin "P$18") (pinfunction "VOUT_P$18") (pintype "passive"))
      (node (ref "MOD2") (pin "P$19") (pinfunction "VOUT_P$19") (pintype "passive"))
      (node (ref "MOD2") (pin "P$20") (pinfunction "VOUT_P$20") (pintype "passive"))
      (node (ref "MOD2") (pin "P$21") (pinfunction "VOUT_P$21") (pintype "passive"))
      (node (ref "MOD2") (pin "P$22") (pinfunction "VOUT_P$22") (pintype "passive"))
      (node (ref "MOD2") (pin "P$23") (pinfunction "VOUT_P$23") (pintype "passive"))
      (node (ref "MOD2") (pin "P$24") (pinfunction "VOUT_P$24") (pintype "passive"))
      (node (ref "MOD2") (pin "P$9") (pinfunction "VOUT_P$9") (pintype "passive"))
    )
    (net (code "29") (name "Net-(IC1-INPUT+)") (class "Default")
      (node (ref "C3") (pin "1") (pinfunction "1_1") (pintype "passive"))
      (node (ref "IC1") (pin "1") (pinfunction "REF_OUT_1") (pintype "bidirectional"))
      (node (ref "IC1") (pin "3") (pinfunction "INPUT+_3") (pintype "bidirectional"))
      (node (ref "IC1") (pin "8") (pinfunction "REF_FEEDBACK_8") (pintype "bidirectional"))
    )
    (net (code "30") (name "Net-(IC1-INPUT-)") (class "Default")
      (node (ref "C27") (pin "1") (pinfunction "1_1") (pintype "passive"))
      (node (ref "IC1") (pin "2") (pinfunction "INPUT-_2") (pintype "bidirectional"))
      (node (ref "R1") (pin "1") (pinfunction "1_1") (pintype "passive"))
      (node (ref "R2") (pin "2") (pinfunction "2_2") (pintype "passive"))
    )
    (net (code "31") (name "Net-(IC2-ADJUST)") (class "Default")
      (node (ref "IC2") (pin "3") (pinfunction "ADJUST_3") (pintype "bidirectional"))
      (node (ref "R3") (pin "1") (pinfunction "1_1") (pintype "passive"))
      (node (ref "R4") (pin "2") (pinfunction "2_2") (pintype "passive"))
    )
    (net (code "32") (name "Net-(IC2-OUTPUT)") (class "Default")
      (node (ref "C4") (pin "2") (pinfunction "2_2") (pintype "passive"))
      (node (ref "D3") (pin "A") (pinfunction "A_A") (pintype "passive"))
      (node (ref "IC2") (pin "2") (pinfunction "OUTPUT_2") (pintype "bidirectional"))
      (node (ref "Q1") (pin "1") (pinfunction "G_1") (pintype "bidirectional"))
      (node (ref "R4") (pin "1") (pinfunction "1_1") (pintype "passive"))
    )
    (net (code "33") (name "Net-(IC3-IP+1)") (class "Default")
      (node (ref "D2") (pin "C") (pinfunction "C_C") (pintype "passive"))
      (node (ref "F1") (pin "3") (pinfunction "2_3") (pintype "passive"))
      (node (ref "F1") (pin "4") (pinfunction "2_4") (pintype "passive"))
      (node (ref "IC3") (pin "1") (pinfunction "IP+1_1") (pintype "bidirectional"))
      (node (ref "IC3") (pin "2") (pinfunction "IP+2_2") (pintype "bidirectional"))
    )
    (net (code "34") (name "Net-(IC4-ADJUST)") (class "Default")
      (node (ref "IC4") (pin "3") (pinfunction "ADJUST_3") (pintype "bidirectional"))
      (node (ref "R13") (pin "1") (pinfunction "1_1") (pintype "passive"))
      (node (ref "R14") (pin "2") (pinfunction "2_2") (pintype "passive"))
    )
    (net (code "35") (name "Net-(IC4-OUTPUT)") (class "Default")
      (node (ref "C16") (pin "2") (pinfunction "2_2") (pintype "passive"))
      (node (ref "D1") (pin "A") (pinfunction "A_A") (pintype "passive"))
      (node (ref "IC4") (pin "2") (pinfunction "OUTPUT_2") (pintype "bidirectional"))
      (node (ref "Q2") (pin "1") (pinfunction "G_1") (pintype "bidirectional"))
      (node (ref "R14") (pin "1") (pinfunction "1_1") (pintype "passive"))
    )
    (net (code "36") (name "Net-(LED1-C)") (class "Default")
      (node (ref "LED1") (pin "2") (pinfunction "C_2") (pintype "passive"))
      (node (ref "R10") (pin "2") (pinfunction "2_2") (pintype "passive"))
    )
    (net (code "37") (name "Net-(LED2-C)") (class "Default")
      (node (ref "LED2") (pin "2") (pinfunction "C_2") (pintype "passive"))
      (node (ref "R11") (pin "2") (pinfunction "2_2") (pintype "passive"))
    )
    (net (code "38") (name "Net-(LED3-C)") (class "Default")
      (node (ref "LED3") (pin "2") (pinfunction "C_2") (pintype "passive"))
      (node (ref "R12") (pin "2") (pinfunction "2_2") (pintype "passive"))
    )
    (net (code "39") (name "REGULATOR_ON") (class "Default")
      (node (ref "C29") (pin "1") (pinfunction "1_1") (pintype "passive"))
      (node (ref "IC1") (pin "6") (pinfunction "OUTPUT_6") (pintype "bidirectional"))
      (node (ref "IC2") (pin "1") (pinfunction "INPUT_1") (pintype "bidirectional"))
    )
    (net (code "40") (name "REVERSE_POLARITY_PROT_OUT") (class "Default")
      (node (ref "C1") (pin "1") (pinfunction "1_1") (pintype "passive"))
      (node (ref "C16") (pin "1") (pinfunction "1_1") (pintype "passive"))
      (node (ref "C28") (pin "1") (pinfunction "1_1") (pintype "passive"))
      (node (ref "C30") (pin "1") (pinfunction "1_1") (pintype "passive"))
      (node (ref "C4") (pin "1") (pinfunction "1_1") (pintype "passive"))
      (node (ref "D1") (pin "C") (pinfunction "C_C") (pintype "passive"))
      (node (ref "D3") (pin "C") (pinfunction "C_C") (pintype "passive"))
      (node (ref "IC1") (pin "7") (pinfunction "SUPPLY+_7") (pintype "bidirectional"))
      (node (ref "Q1") (pin "3") (pinfunction "S_3") (pintype "bidirectional"))
      (node (ref "Q2") (pin "3") (pinfunction "S_3") (pintype "bidirectional"))
      (node (ref "R1") (pin "2") (pinfunction "2_2") (pintype "passive"))
      (node (ref "R13") (pin "2") (pinfunction "2_2") (pintype "passive"))
      (node (ref "R3") (pin "2") (pinfunction "2_2") (pintype "passive"))
    )
    (net (code "41") (name "VCC") (class "Default")
      (node (ref "C31") (pin "1") (pinfunction "1_1") (pintype "passive"))
      (node (ref "C5") (pin "1") (pinfunction "1_1") (pintype "passive"))
      (node (ref "C6") (pin "1") (pinfunction "1_1") (pintype "passive"))
      (node (ref "C7") (pin "+") (pinfunction "+_+") (pintype "passive"))
      (node (ref "C8") (pin "+") (pinfunction "+_+") (pintype "passive"))
      (node (ref "CON9") (pin "8") (pinfunction "8_8") (pintype "passive"))
      (node (ref "LED1") (pin "1") (pinfunction "A_1") (pintype "passive"))
      (node (ref "MOD1") (pin "P$1") (pinfunction "VIN_P$1") (pintype "passive"))
      (node (ref "MOD1") (pin "P$2") (pinfunction "VIN_P$2") (pintype "passive"))
      (node (ref "MOD1") (pin "P$3") (pinfunction "VIN_P$3") (pintype "passive"))
      (node (ref "MOD1") (pin "P$4") (pinfunction "VIN_P$4") (pintype "passive"))
      (node (ref "MOD1") (pin "P$5") (pinfunction "VIN_P$5") (pintype "passive"))
      (node (ref "MOD1") (pin "P$6") (pinfunction "VIN_P$6") (pintype "passive"))
      (node (ref "MOD1") (pin "P$7") (pinfunction "VIN_P$7") (pintype "passive"))
      (node (ref "MOD1") (pin "P$8") (pinfunction "VIN_P$8") (pintype "passive"))
      (node (ref "MOD2") (pin "P$1") (pinfunction "VIN_P$1") (pintype "passive"))
      (node (ref "MOD2") (pin "P$2") (pinfunction "VIN_P$2") (pintype "passive"))
      (node (ref "MOD2") (pin "P$3") (pinfunction "VIN_P$3") (pintype "passive"))
      (node (ref "MOD2") (pin "P$4") (pinfunction "VIN_P$4") (pintype "passive"))
      (node (ref "MOD2") (pin "P$5") (pinfunction "VIN_P$5") (pintype "passive"))
      (node (ref "MOD2") (pin "P$6") (pinfunction "VIN_P$6") (pintype "passive"))
      (node (ref "MOD2") (pin "P$7") (pinfunction "VIN_P$7") (pintype "passive"))
      (node (ref "MOD2") (pin "P$8") (pinfunction "VIN_P$8") (pintype "passive"))
      (node (ref "Q1") (pin "2") (pinfunction "D_2") (pintype "bidirectional"))
    )
    (net (code "42") (name "unconnected-(IC1-BALANCE-Pad5)") (class "Default")
      (node (ref "IC1") (pin "5") (pinfunction "BALANCE_5") (pintype "bidirectional"))
    )
  )
)
